# motor.net
KiCad netlist of a schematic drawn in EAGLE
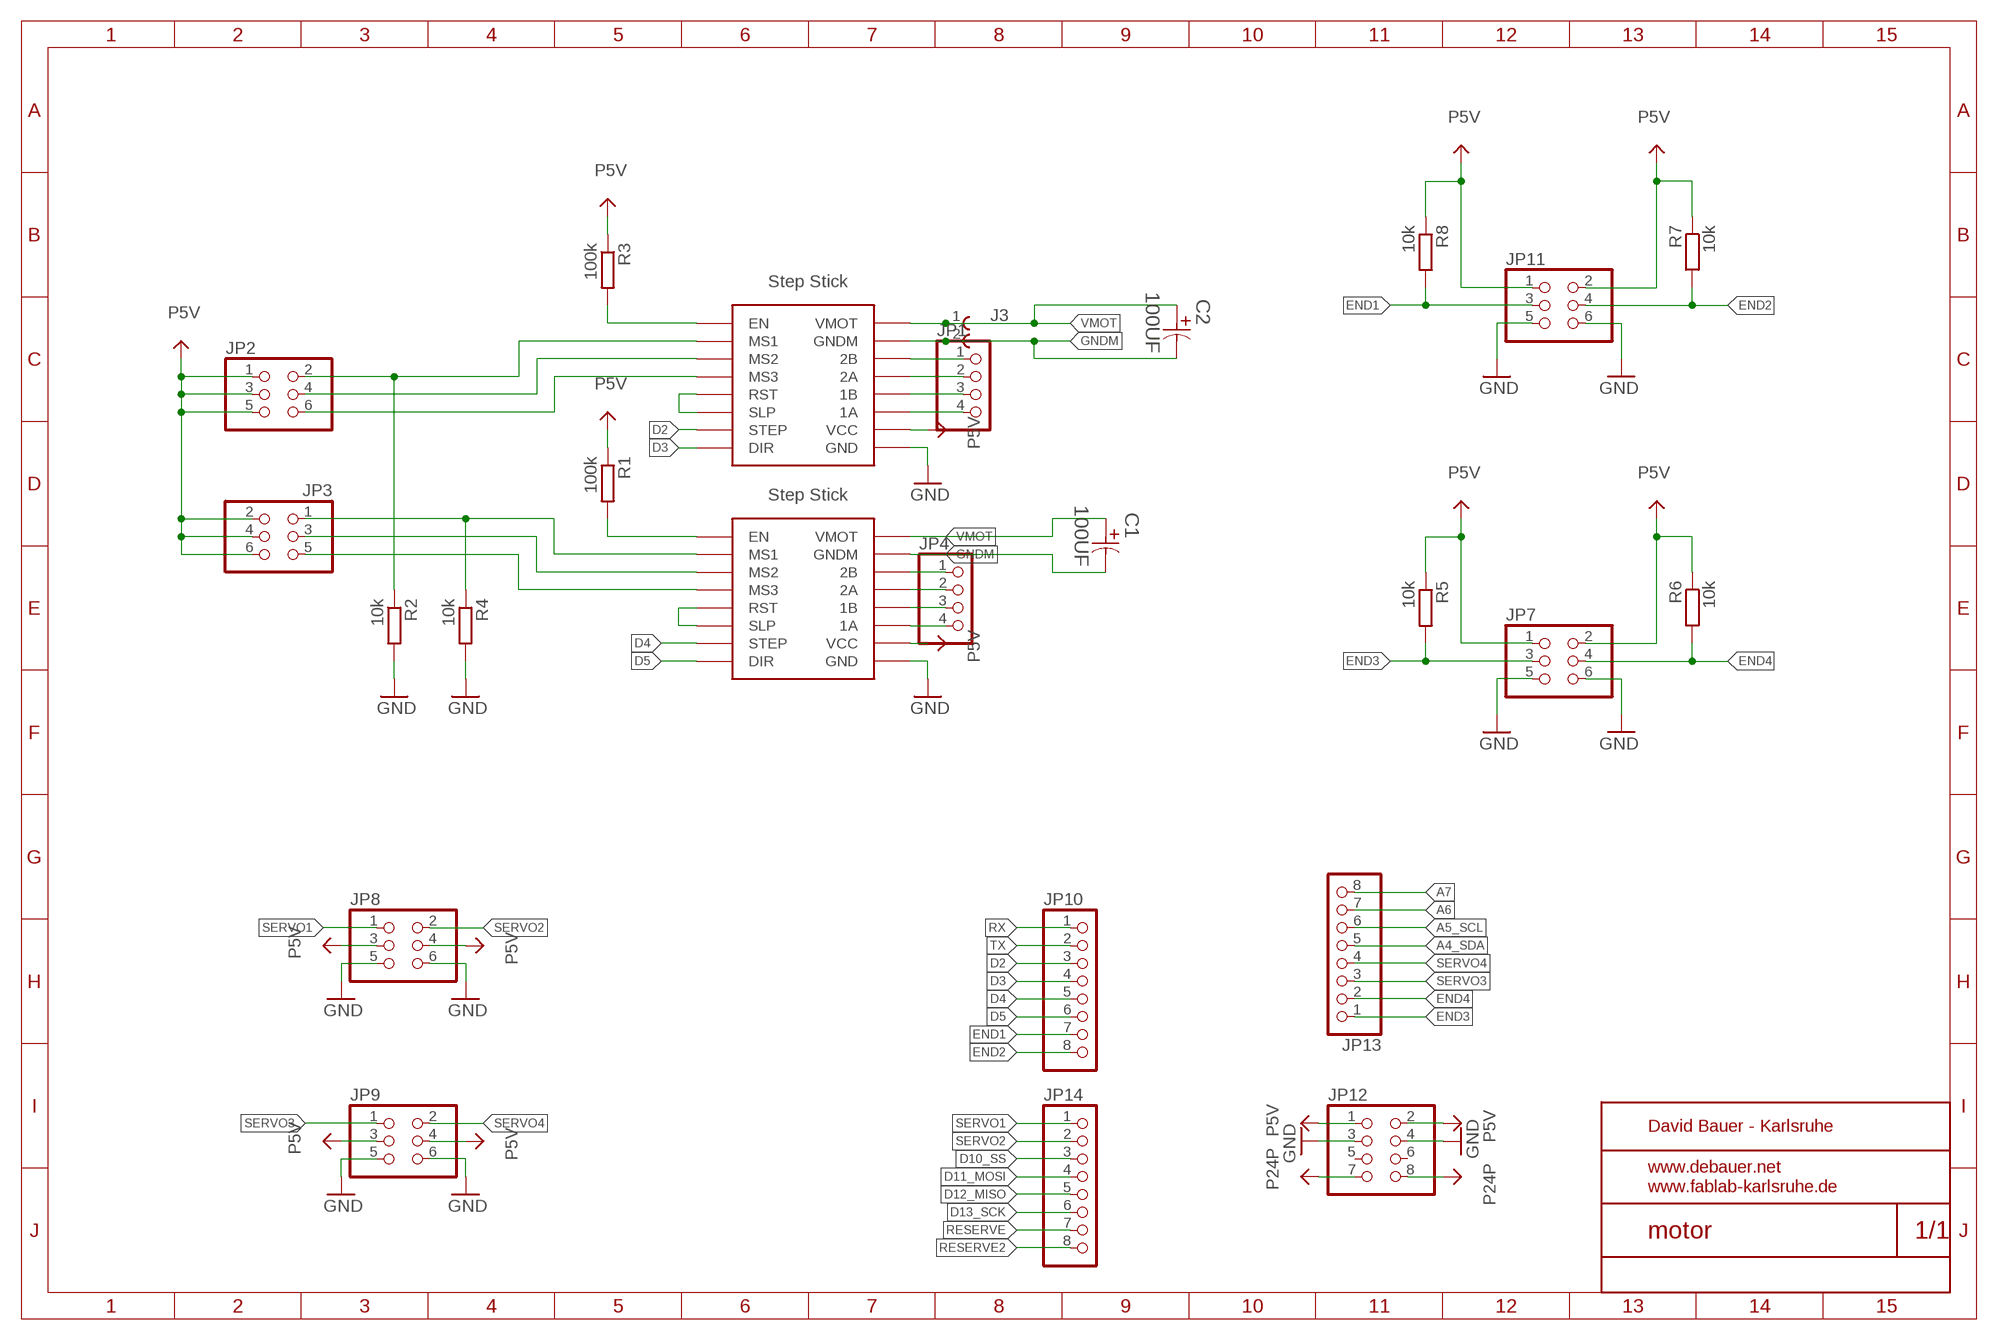
[diagram p0: schematic, sheet 1]

(export (version "E")
  (design (tool "Eeschema 10.0.6"))
  (components
    (comp (ref "C1")
      (value "100UF")
      (footprint "eagle-import:CAPAE830X1050N")
      (fields (field (name "MPN") "EEE-FK1V101P") (field (name "TOLERANCE") "±20 %"))
      (libsource (lib "eagle-import") (part "EEE--CASE-FFK1V101P"))
    )
    (comp (ref "C2")
      (value "100UF")
      (footprint "eagle-import:CAPAE830X1050N")
      (fields (field (name "MPN") "EEE-FK1V101P") (field (name "TOLERANCE") "±20 %"))
      (libsource (lib "eagle-import") (part "EEE--CASE-FFK1V101P"))
    )
    (comp (ref "J3")
      (value "691312510002")
      (footprint "eagle-import:691312510002")
      (libsource (lib "eagle-import") (part "691312510002"))
    )
    (comp (ref "JP1")
      (value "PINHD-1X4/90")
      (footprint "eagle-import:1X04_90")
      (libsource (lib "eagle-import") (part "PINHD-1X4/90"))
    )
    (comp (ref "JP2")
      (value "PINHD-2X3")
      (footprint "eagle-import:2X03")
      (libsource (lib "eagle-import") (part "PINHD-2X3"))
    )
    (comp (ref "JP3")
      (value "PINHD-2X3")
      (footprint "eagle-import:2X03")
      (libsource (lib "eagle-import") (part "PINHD-2X3"))
    )
    (comp (ref "JP4")
      (value "PINHD-1X4/90")
      (footprint "eagle-import:1X04_90")
      (libsource (lib "eagle-import") (part "PINHD-1X4/90"))
    )
    (comp (ref "JP7")
      (value "PINHD-2X3/90")
      (footprint "eagle-import:2X03_90")
      (libsource (lib "eagle-import") (part "PINHD-2X3/90"))
    )
    (comp (ref "JP8")
      (value "PINHD-2X3/90")
      (footprint "eagle-import:2X03_90")
      (libsource (lib "eagle-import") (part "PINHD-2X3/90"))
    )
    (comp (ref "JP9")
      (value "PINHD-2X3/90")
      (footprint "eagle-import:2X03_90")
      (libsource (lib "eagle-import") (part "PINHD-2X3/90"))
    )
    (comp (ref "JP10")
      (value "PINHD-1X8")
      (footprint "eagle-import:1X08")
      (libsource (lib "eagle-import") (part "PINHD-1X8"))
    )
    (comp (ref "JP11")
      (value "PINHD-2X3/90")
      (footprint "eagle-import:2X03_90")
      (libsource (lib "eagle-import") (part "PINHD-2X3/90"))
    )
    (comp (ref "JP12")
      (value "PINHD-2X4")
      (footprint "eagle-import:2X04")
      (libsource (lib "eagle-import") (part "PINHD-2X4"))
    )
    (comp (ref "JP13")
      (value "PINHD-1X8")
      (footprint "eagle-import:1X08")
      (libsource (lib "eagle-import") (part "PINHD-1X8"))
    )
    (comp (ref "JP14")
      (value "PINHD-1X8")
      (footprint "eagle-import:1X08")
      (libsource (lib "eagle-import") (part "PINHD-1X8"))
    )
    (comp (ref "R1")
      (value "100k")
      (footprint "eagle-import:R0805")
      (libsource (lib "eagle-import") (part "R-EU_R0805"))
    )
    (comp (ref "R2")
      (value "10k")
      (footprint "eagle-import:R0805")
      (libsource (lib "eagle-import") (part "R-EU_R0805"))
    )
    (comp (ref "R3")
      (value "100k")
      (footprint "eagle-import:R0805")
      (libsource (lib "eagle-import") (part "R-EU_R0805"))
    )
    (comp (ref "R4")
      (value "10k")
      (footprint "eagle-import:R0805")
      (libsource (lib "eagle-import") (part "R-EU_R0805"))
    )
    (comp (ref "R5")
      (value "10k")
      (footprint "eagle-import:R0805")
      (libsource (lib "eagle-import") (part "R-EU_R0805"))
    )
    (comp (ref "R6")
      (value "10k")
      (footprint "eagle-import:R0805")
      (libsource (lib "eagle-import") (part "R-EU_R0805"))
    )
    (comp (ref "R7")
      (value "10k")
      (footprint "eagle-import:R0805")
      (libsource (lib "eagle-import") (part "R-EU_R0805"))
    )
    (comp (ref "R8")
      (value "10k")
      (footprint "eagle-import:R0805")
      (libsource (lib "eagle-import") (part "R-EU_R0805"))
    )
    (comp (ref "U$1")
      (value "STEP-STICK")
      (footprint "eagle-import:STEP-STICK")
      (libsource (lib "eagle-import") (part "STEP-STICK"))
    )
    (comp (ref "U$2")
      (value "STEP-STICK")
      (footprint "eagle-import:STEP-STICK")
      (libsource (lib "eagle-import") (part "STEP-STICK"))
    )
  )
  (nets
    (net (code "1") (name "A4_SDA") (class "Default")
      (node (ref "JP13") (pin "5") (pinfunction "5_5") (pintype "passive"))
    )
    (net (code "2") (name "A5_SCL") (class "Default")
      (node (ref "JP13") (pin "6") (pinfunction "6_6") (pintype "passive"))
    )
    (net (code "3") (name "A6") (class "Default")
      (node (ref "JP13") (pin "7") (pinfunction "7_7") (pintype "passive"))
    )
    (net (code "4") (name "A7") (class "Default")
      (node (ref "JP13") (pin "8") (pinfunction "8_8") (pintype "passive"))
    )
    (net (code "5") (name "D2") (class "Default")
      (node (ref "JP10") (pin "3") (pinfunction "3_3") (pintype "passive"))
      (node (ref "U$2") (pin "SPT") (pinfunction "STEP_SPT") (pintype "bidirectional"))
    )
    (net (code "6") (name "D3") (class "Default")
      (node (ref "JP10") (pin "4") (pinfunction "4_4") (pintype "passive"))
      (node (ref "U$2") (pin "DIR") (pinfunction "DIR_DIR") (pintype "bidirectional"))
    )
    (net (code "7") (name "D4") (class "Default")
      (node (ref "JP10") (pin "5") (pinfunction "5_5") (pintype "passive"))
      (node (ref "U$1") (pin "SPT") (pinfunction "STEP_SPT") (pintype "bidirectional"))
    )
    (net (code "8") (name "D5") (class "Default")
      (node (ref "JP10") (pin "6") (pinfunction "6_6") (pintype "passive"))
      (node (ref "U$1") (pin "DIR") (pinfunction "DIR_DIR") (pintype "bidirectional"))
    )
    (net (code "9") (name "D10_SS") (class "Default")
      (node (ref "JP14") (pin "3") (pinfunction "3_3") (pintype "passive"))
    )
    (net (code "10") (name "D11_MOSI") (class "Default")
      (node (ref "JP14") (pin "4") (pinfunction "4_4") (pintype "passive"))
    )
    (net (code "11") (name "D12_MISO") (class "Default")
      (node (ref "JP14") (pin "5") (pinfunction "5_5") (pintype "passive"))
    )
    (net (code "12") (name "D13_SCK") (class "Default")
      (node (ref "JP14") (pin "6") (pinfunction "6_6") (pintype "passive"))
    )
    (net (code "13") (name "END1") (class "Default")
      (node (ref "JP10") (pin "7") (pinfunction "7_7") (pintype "passive"))
      (node (ref "JP11") (pin "3") (pinfunction "3_3") (pintype "passive"))
      (node (ref "R8") (pin "2") (pinfunction "2_2") (pintype "passive"))
    )
    (net (code "14") (name "END2") (class "Default")
      (node (ref "JP10") (pin "8") (pinfunction "8_8") (pintype "passive"))
      (node (ref "JP11") (pin "4") (pinfunction "4_4") (pintype "passive"))
      (node (ref "R7") (pin "2") (pinfunction "2_2") (pintype "passive"))
    )
    (net (code "15") (name "END3") (class "Default")
      (node (ref "JP13") (pin "1") (pinfunction "1_1") (pintype "passive"))
      (node (ref "JP7") (pin "3") (pinfunction "3_3") (pintype "passive"))
      (node (ref "R5") (pin "2") (pinfunction "2_2") (pintype "passive"))
    )
    (net (code "16") (name "END4") (class "Default")
      (node (ref "JP13") (pin "2") (pinfunction "2_2") (pintype "passive"))
      (node (ref "JP7") (pin "4") (pinfunction "4_4") (pintype "passive"))
      (node (ref "R6") (pin "2") (pinfunction "2_2") (pintype "passive"))
    )
    (net (code "17") (name "GND") (class "Default")
      (node (ref "JP11") (pin "5") (pinfunction "5_5") (pintype "passive"))
      (node (ref "JP11") (pin "6") (pinfunction "6_6") (pintype "passive"))
      (node (ref "JP12") (pin "3") (pinfunction "3_3") (pintype "passive"))
      (node (ref "JP12") (pin "4") (pinfunction "4_4") (pintype "passive"))
      (node (ref "JP7") (pin "5") (pinfunction "5_5") (pintype "passive"))
      (node (ref "JP7") (pin "6") (pinfunction "6_6") (pintype "passive"))
      (node (ref "JP8") (pin "5") (pinfunction "5_5") (pintype "passive"))
      (node (ref "JP8") (pin "6") (pinfunction "6_6") (pintype "passive"))
      (node (ref "JP9") (pin "5") (pinfunction "5_5") (pintype "passive"))
      (node (ref "JP9") (pin "6") (pinfunction "6_6") (pintype "passive"))
      (node (ref "R2") (pin "2") (pinfunction "2_2") (pintype "passive"))
      (node (ref "R4") (pin "2") (pinfunction "2_2") (pintype "passive"))
      (node (ref "U$1") (pin "GND") (pinfunction "GND_GND") (pintype "bidirectional"))
      (node (ref "U$2") (pin "GND") (pinfunction "GND_GND") (pintype "bidirectional"))
    )
    (net (code "18") (name "GNDM") (class "Default")
      (node (ref "C1") (pin "2") (pinfunction "2_2") (pintype "passive"))
      (node (ref "C2") (pin "2") (pinfunction "2_2") (pintype "passive"))
      (node (ref "J3") (pin "2") (pinfunction "2_2") (pintype "passive"))
      (node (ref "U$1") (pin "GNDM") (pinfunction "GNDM_GNDM") (pintype "bidirectional"))
      (node (ref "U$2") (pin "GNDM") (pinfunction "GNDM_GNDM") (pintype "bidirectional"))
    )
    (net (code "19") (name "Net-(JP1-Pad1)") (class "Default")
      (node (ref "JP1") (pin "1") (pinfunction "1_1") (pintype "passive"))
      (node (ref "U$2") (pin "2B") (pinfunction "2B_2B") (pintype "bidirectional"))
    )
    (net (code "20") (name "Net-(JP1-Pad2)") (class "Default")
      (node (ref "JP1") (pin "2") (pinfunction "2_2") (pintype "passive"))
      (node (ref "U$2") (pin "2A") (pinfunction "2A_2A") (pintype "bidirectional"))
    )
    (net (code "21") (name "Net-(JP1-Pad3)") (class "Default")
      (node (ref "JP1") (pin "3") (pinfunction "3_3") (pintype "passive"))
      (node (ref "U$2") (pin "1B") (pinfunction "1B_1B") (pintype "bidirectional"))
    )
    (net (code "22") (name "Net-(JP1-Pad4)") (class "Default")
      (node (ref "JP1") (pin "4") (pinfunction "4_4") (pintype "passive"))
      (node (ref "U$2") (pin "1A") (pinfunction "1A_1A") (pintype "bidirectional"))
    )
    (net (code "23") (name "Net-(JP2-Pad2)") (class "Default")
      (node (ref "JP2") (pin "2") (pinfunction "2_2") (pintype "passive"))
      (node (ref "R2") (pin "1") (pinfunction "1_1") (pintype "passive"))
      (node (ref "U$2") (pin "MS1") (pinfunction "MS1_MS1") (pintype "bidirectional"))
    )
    (net (code "24") (name "Net-(JP2-Pad4)") (class "Default")
      (node (ref "JP2") (pin "4") (pinfunction "4_4") (pintype "passive"))
      (node (ref "U$2") (pin "MS2") (pinfunction "MS2_MS2") (pintype "bidirectional"))
    )
    (net (code "25") (name "Net-(JP2-Pad6)") (class "Default")
      (node (ref "JP2") (pin "6") (pinfunction "6_6") (pintype "passive"))
      (node (ref "U$2") (pin "MS3") (pinfunction "MS3_MS3") (pintype "bidirectional"))
    )
    (net (code "26") (name "Net-(JP3-Pad1)") (class "Default")
      (node (ref "JP3") (pin "1") (pinfunction "1_1") (pintype "passive"))
      (node (ref "R4") (pin "1") (pinfunction "1_1") (pintype "passive"))
      (node (ref "U$1") (pin "MS1") (pinfunction "MS1_MS1") (pintype "bidirectional"))
    )
    (net (code "27") (name "Net-(JP3-Pad3)") (class "Default")
      (node (ref "JP3") (pin "3") (pinfunction "3_3") (pintype "passive"))
      (node (ref "U$1") (pin "MS2") (pinfunction "MS2_MS2") (pintype "bidirectional"))
    )
    (net (code "28") (name "Net-(JP3-Pad5)") (class "Default")
      (node (ref "JP3") (pin "5") (pinfunction "5_5") (pintype "passive"))
      (node (ref "U$1") (pin "MS3") (pinfunction "MS3_MS3") (pintype "bidirectional"))
    )
    (net (code "29") (name "Net-(JP4-Pad1)") (class "Default")
      (node (ref "JP4") (pin "1") (pinfunction "1_1") (pintype "passive"))
      (node (ref "U$1") (pin "2B") (pinfunction "2B_2B") (pintype "bidirectional"))
    )
    (net (code "30") (name "Net-(JP4-Pad2)") (class "Default")
      (node (ref "JP4") (pin "2") (pinfunction "2_2") (pintype "passive"))
      (node (ref "U$1") (pin "2A") (pinfunction "2A_2A") (pintype "bidirectional"))
    )
    (net (code "31") (name "Net-(JP4-Pad3)") (class "Default")
      (node (ref "JP4") (pin "3") (pinfunction "3_3") (pintype "passive"))
      (node (ref "U$1") (pin "1B") (pinfunction "1B_1B") (pintype "bidirectional"))
    )
    (net (code "32") (name "Net-(JP4-Pad4)") (class "Default")
      (node (ref "JP4") (pin "4") (pinfunction "4_4") (pintype "passive"))
      (node (ref "U$1") (pin "1A") (pinfunction "1A_1A") (pintype "bidirectional"))
    )
    (net (code "33") (name "Net-(R1-Pad2)") (class "Default")
      (node (ref "R1") (pin "2") (pinfunction "2_2") (pintype "passive"))
      (node (ref "U$1") (pin "EN") (pinfunction "EN_EN") (pintype "bidirectional"))
    )
    (net (code "34") (name "Net-(R3-Pad2)") (class "Default")
      (node (ref "R3") (pin "2") (pinfunction "2_2") (pintype "passive"))
      (node (ref "U$2") (pin "EN") (pinfunction "EN_EN") (pintype "bidirectional"))
    )
    (net (code "35") (name "Net-(U$1-PadRST)") (class "Default")
      (node (ref "U$1") (pin "RST") (pinfunction "RST_RST") (pintype "bidirectional"))
      (node (ref "U$1") (pin "SLP") (pinfunction "SLP_SLP") (pintype "bidirectional"))
    )
    (net (code "36") (name "Net-(U$2-PadRST)") (class "Default")
      (node (ref "U$2") (pin "RST") (pinfunction "RST_RST") (pintype "bidirectional"))
      (node (ref "U$2") (pin "SLP") (pinfunction "SLP_SLP") (pintype "bidirectional"))
    )
    (net (code "37") (name "P5V") (class "Default")
      (node (ref "JP11") (pin "1") (pinfunction "1_1") (pintype "passive"))
      (node (ref "JP11") (pin "2") (pinfunction "2_2") (pintype "passive"))
      (node (ref "JP12") (pin "1") (pinfunction "1_1") (pintype "passive"))
      (node (ref "JP12") (pin "2") (pinfunction "2_2") (pintype "passive"))
      (node (ref "JP2") (pin "1") (pinfunction "1_1") (pintype "passive"))
      (node (ref "JP2") (pin "3") (pinfunction "3_3") (pintype "passive"))
      (node (ref "JP2") (pin "5") (pinfunction "5_5") (pintype "passive"))
      (node (ref "JP3") (pin "2") (pinfunction "2_2") (pintype "passive"))
      (node (ref "JP3") (pin "4") (pinfunction "4_4") (pintype "passive"))
      (node (ref "JP3") (pin "6") (pinfunction "6_6") (pintype "passive"))
      (node (ref "JP7") (pin "1") (pinfunction "1_1") (pintype "passive"))
      (node (ref "JP7") (pin "2") (pinfunction "2_2") (pintype "passive"))
      (node (ref "JP8") (pin "3") (pinfunction "3_3") (pintype "passive"))
      (node (ref "JP8") (pin "4") (pinfunction "4_4") (pintype "passive"))
      (node (ref "JP9") (pin "3") (pinfunction "3_3") (pintype "passive"))
      (node (ref "JP9") (pin "4") (pinfunction "4_4") (pintype "passive"))
      (node (ref "R1") (pin "1") (pinfunction "1_1") (pintype "passive"))
      (node (ref "R3") (pin "1") (pinfunction "1_1") (pintype "passive"))
      (node (ref "R5") (pin "1") (pinfunction "1_1") (pintype "passive"))
      (node (ref "R6") (pin "1") (pinfunction "1_1") (pintype "passive"))
      (node (ref "R7") (pin "1") (pinfunction "1_1") (pintype "passive"))
      (node (ref "R8") (pin "1") (pinfunction "1_1") (pintype "passive"))
      (node (ref "U$1") (pin "VCC") (pinfunction "VCC_VCC") (pintype "bidirectional"))
      (node (ref "U$2") (pin "VCC") (pinfunction "VCC_VCC") (pintype "bidirectional"))
    )
    (net (code "38") (name "P24P") (class "Default")
      (node (ref "JP12") (pin "7") (pinfunction "7_7") (pintype "passive"))
      (node (ref "JP12") (pin "8") (pinfunction "8_8") (pintype "passive"))
    )
    (net (code "39") (name "RESERVE") (class "Default")
      (node (ref "JP14") (pin "7") (pinfunction "7_7") (pintype "passive"))
    )
    (net (code "40") (name "RESERVE2") (class "Default")
      (node (ref "JP14") (pin "8") (pinfunction "8_8") (pintype "passive"))
    )
    (net (code "41") (name "RX") (class "Default")
      (node (ref "JP10") (pin "1") (pinfunction "1_1") (pintype "passive"))
    )
    (net (code "42") (name "SERVO1") (class "Default")
      (node (ref "JP14") (pin "1") (pinfunction "1_1") (pintype "passive"))
      (node (ref "JP8") (pin "1") (pinfunction "1_1") (pintype "passive"))
    )
    (net (code "43") (name "SERVO2") (class "Default")
      (node (ref "JP14") (pin "2") (pinfunction "2_2") (pintype "passive"))
      (node (ref "JP8") (pin "2") (pinfunction "2_2") (pintype "passive"))
    )
    (net (code "44") (name "SERVO3") (class "Default")
      (node (ref "JP13") (pin "3") (pinfunction "3_3") (pintype "passive"))
      (node (ref "JP9") (pin "1") (pinfunction "1_1") (pintype "passive"))
    )
    (net (code "45") (name "SERVO4") (class "Default")
      (node (ref "JP13") (pin "4") (pinfunction "4_4") (pintype "passive"))
      (node (ref "JP9") (pin "2") (pinfunction "2_2") (pintype "passive"))
    )
    (net (code "46") (name "TX") (class "Default")
      (node (ref "JP10") (pin "2") (pinfunction "2_2") (pintype "passive"))
    )
    (net (code "47") (name "VMOT") (class "Default")
      (node (ref "C1") (pin "1") (pinfunction "1_1") (pintype "passive"))
      (node (ref "C2") (pin "1") (pinfunction "1_1") (pintype "passive"))
      (node (ref "J3") (pin "1") (pinfunction "1_1") (pintype "passive"))
      (node (ref "U$1") (pin "VMOT") (pinfunction "VMOT_VMOT") (pintype "bidirectional"))
      (node (ref "U$2") (pin "VMOT") (pinfunction "VMOT_VMOT") (pintype "bidirectional"))
    )
    (net (code "48") (name "unconnected-(JP12-Pad5)") (class "Default")
      (node (ref "JP12") (pin "5") (pinfunction "5_5") (pintype "passive"))
    )
    (net (code "49") (name "unconnected-(JP12-Pad6)") (class "Default")
      (node (ref "JP12") (pin "6") (pinfunction "6_6") (pintype "passive"))
    )
  )
)
